# buzzer_12v_limiter.net
KiCad netlist of a schematic drawn in EAGLE
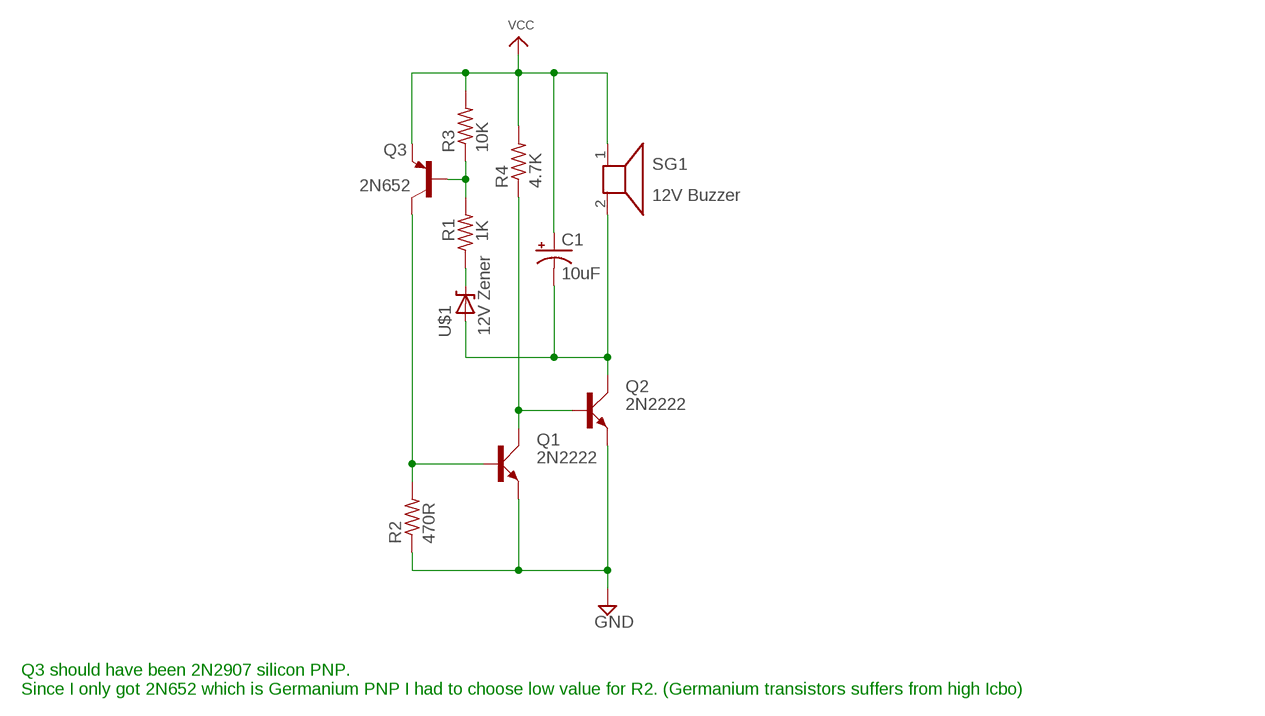
[diagram p0: schematic, sheet 1]

(export (version "E")
  (design (tool "Eeschema 10.0.6"))
  (components
    (comp (ref "C1")
      (value "10uF")
      (footprint "eagle-import:PANASONIC_H13")
      (libsource (lib "eagle-import") (part "100UF-63V-20%(ELECT)"))
    )
    (comp (ref "Q1")
      (value "2N2222")
      (footprint "eagle-import:TO18A")
      (libsource (lib "eagle-import") (part "2N2222"))
    )
    (comp (ref "Q2")
      (value "2N2222")
      (footprint "eagle-import:TO18A")
      (libsource (lib "eagle-import") (part "2N2222"))
    )
    (comp (ref "Q3")
      (value "2N652")
      (footprint "eagle-import:TO18")
      (libsource (lib "eagle-import") (part "2N2907"))
    )
    (comp (ref "R1")
      (value "1K")
      (footprint "eagle-import:0805-THM")
      (libsource (lib "eagle-import") (part "FLIPFLOP-RES"))
    )
    (comp (ref "R2")
      (value "470R")
      (footprint "eagle-import:0805-THM")
      (libsource (lib "eagle-import") (part "FLIPFLOP-RES"))
    )
    (comp (ref "R3")
      (value "10K")
      (footprint "eagle-import:0805-THM")
      (libsource (lib "eagle-import") (part "FLIPFLOP-RES"))
    )
    (comp (ref "R4")
      (value "4.7K")
      (footprint "eagle-import:0805-THM")
      (libsource (lib "eagle-import") (part "FLIPFLOP-RES"))
    )
    (comp (ref "SG1")
      (value "12V Buzzer")
      (footprint "eagle-import:F_SMX")
      (libsource (lib "eagle-import") (part "F/SMX"))
    )
    (comp (ref "U$1")
      (value "12V Zener")
      (footprint "eagle-import:DIODE-ZENER")
      (libsource (lib "eagle-import") (part "DIODE-ZENERPTH"))
    )
  )
  (nets
    (net (code "1") (name "GND") (class "Default")
      (node (ref "Q1") (pin "E") (pinfunction "E_E") (pintype "passive"))
      (node (ref "Q2") (pin "E") (pinfunction "E_E") (pintype "passive"))
      (node (ref "R2") (pin "1") (pinfunction "1_1") (pintype "passive"))
    )
    (net (code "2") (name "Net-(Q1-PadC)") (class "Default")
      (node (ref "Q1") (pin "C") (pinfunction "C_C") (pintype "passive"))
      (node (ref "Q2") (pin "B") (pinfunction "B_B") (pintype "passive"))
      (node (ref "R4") (pin "1") (pinfunction "1_1") (pintype "passive"))
    )
    (net (code "3") (name "Net-(Q3-B)") (class "Default")
      (node (ref "Q3") (pin "2") (pinfunction "B_2") (pintype "passive"))
      (node (ref "R1") (pin "2") (pinfunction "2_2") (pintype "passive"))
      (node (ref "R3") (pin "1") (pinfunction "1_1") (pintype "passive"))
    )
    (net (code "4") (name "Net-(Q3-C)") (class "Default")
      (node (ref "Q1") (pin "B") (pinfunction "B_B") (pintype "passive"))
      (node (ref "Q3") (pin "3") (pinfunction "C_3") (pintype "passive"))
      (node (ref "R2") (pin "2") (pinfunction "2_2") (pintype "passive"))
    )
    (net (code "5") (name "Net-(U$1-A)") (class "Default")
      (node (ref "C1") (pin "-") (pinfunction "-_-") (pintype "passive"))
      (node (ref "Q2") (pin "C") (pinfunction "C_C") (pintype "passive"))
      (node (ref "SG1") (pin "2") (pinfunction "2_2") (pintype "passive"))
      (node (ref "U$1") (pin "P$2") (pinfunction "A_P$2") (pintype "passive"))
    )
    (net (code "6") (name "Net-(U$1-C)") (class "Default")
      (node (ref "R1") (pin "1") (pinfunction "1_1") (pintype "passive"))
      (node (ref "U$1") (pin "P$1") (pinfunction "C_P$1") (pintype "passive"))
    )
    (net (code "7") (name "VCC") (class "Default")
      (node (ref "C1") (pin "+") (pinfunction "+_+") (pintype "passive"))
      (node (ref "Q3") (pin "1") (pinfunction "E_1") (pintype "passive"))
      (node (ref "R3") (pin "2") (pinfunction "2_2") (pintype "passive"))
      (node (ref "R4") (pin "2") (pinfunction "2_2") (pintype "passive"))
      (node (ref "SG1") (pin "1") (pinfunction "1_1") (pintype "passive"))
    )
  )
)
